# detector_t85-pu.net
KiCad netlist of a schematic drawn in EAGLE
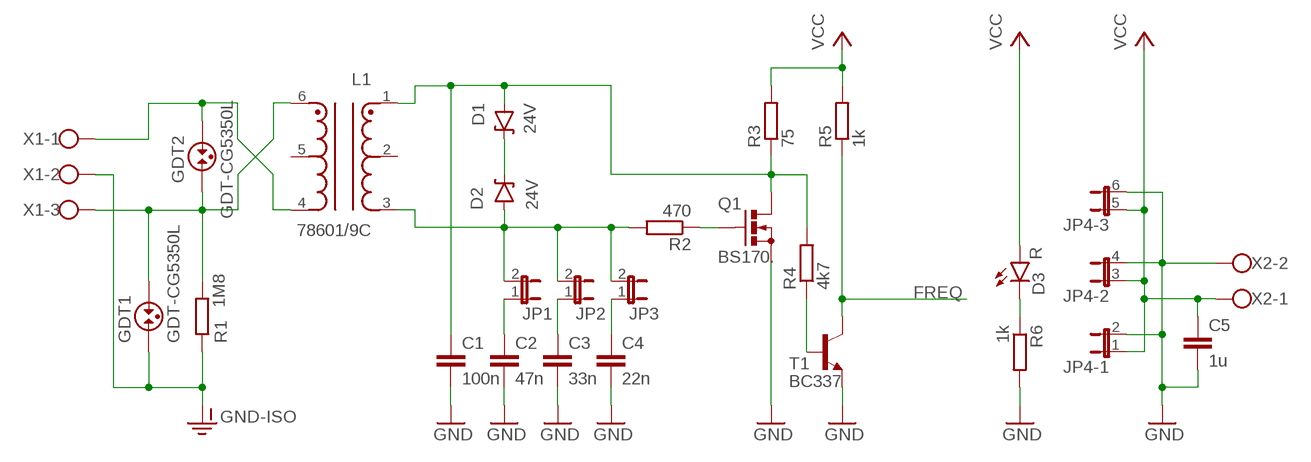
[diagram p0: schematic, sheet 1]
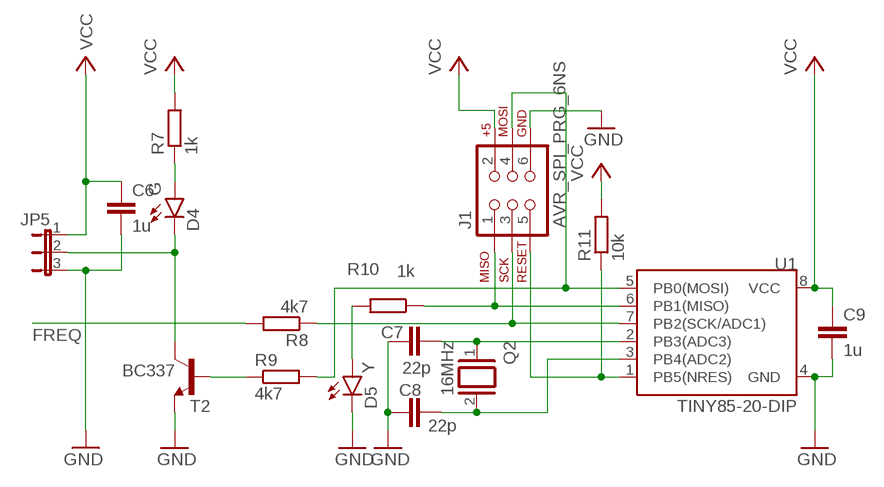
[diagram p1: schematic, sheet 2]

(export (version "E")
  (design (tool "Eeschema 10.0.6"))
  (components
    (comp (ref "C1")
      (value "100n")
      (footprint "eagle-import:C050-024X044")
      (libsource (lib "eagle-import") (part "resistor_C-EU050-024X044"))
    )
    (comp (ref "C2")
      (value "47n")
      (footprint "eagle-import:C050-024X044")
      (libsource (lib "eagle-import") (part "resistor_C-EU050-024X044"))
    )
    (comp (ref "C3")
      (value "33n")
      (footprint "eagle-import:C050-024X044")
      (libsource (lib "eagle-import") (part "resistor_C-EU050-024X044"))
    )
    (comp (ref "C4")
      (value "22n")
      (footprint "eagle-import:C050-024X044")
      (libsource (lib "eagle-import") (part "resistor_C-EU050-024X044"))
    )
    (comp (ref "C5")
      (value "1u")
      (footprint "eagle-import:C050-025X075")
      (libsource (lib "eagle-import") (part "C-EU050-025X075"))
    )
    (comp (ref "D1")
      (value "24V")
      (footprint "eagle-import:DIODE-BZT52")
      (libsource (lib "eagle-import") (part "DIODE-ZENER"))
    )
    (comp (ref "D2")
      (value "24V")
      (footprint "eagle-import:DIODE-BZT52")
      (libsource (lib "eagle-import") (part "DIODE-ZENER"))
    )
    (comp (ref "D3")
      (value "R")
      (footprint "eagle-import:LED3MM")
      (libsource (lib "eagle-import") (part "LED3MM"))
    )
    (comp (ref "GDT1")
      (value "GDT-CG5350L")
      (footprint "eagle-import:CG5350L")
      (libsource (lib "eagle-import") (part "GDT-CG5350L"))
    )
    (comp (ref "GDT2")
      (value "GDT-CG5350L")
      (footprint "eagle-import:CG5350L")
      (libsource (lib "eagle-import") (part "GDT-CG5350L"))
    )
    (comp (ref "JP1")
      (value "JUMPER-2PTH")
      (footprint "eagle-import:1X02")
      (libsource (lib "eagle-import") (part "JUMPER-2PTH"))
    )
    (comp (ref "JP2")
      (value "JUMPER-2PTH")
      (footprint "eagle-import:1X02")
      (libsource (lib "eagle-import") (part "JUMPER-2PTH"))
    )
    (comp (ref "JP3")
      (value "JUMPER-2PTH")
      (footprint "eagle-import:1X02")
      (libsource (lib "eagle-import") (part "JUMPER-2PTH"))
    )
    (comp (ref "JP4")
      (value "JP3QE")
      (footprint "eagle-import:JP3Q")
      (libsource (lib "eagle-import") (part "JP3QE"))
    )
    (comp (ref "L1")
      (value "78601/9C")
      (footprint "eagle-import:78601_9C")
      (libsource (lib "eagle-import") (part "78601/9C"))
    )
    (comp (ref "Q1")
      (value "BS170.")
      (footprint "eagle-import:TO92-DGS")
      (libsource (lib "eagle-import") (part "BS170."))
    )
    (comp (ref "R1")
      (value "1M8")
      (footprint "eagle-import:0204_5")
      (libsource (lib "eagle-import") (part "R-EU_0204/5"))
    )
    (comp (ref "R2")
      (value "470")
      (footprint "eagle-import:0204_5")
      (libsource (lib "eagle-import") (part "R-EU_0204/5"))
    )
    (comp (ref "R3")
      (value "75")
      (footprint "eagle-import:0204_7")
      (libsource (lib "eagle-import") (part "R-EU_0204/7"))
    )
    (comp (ref "R4")
      (value "4k7")
      (footprint "eagle-import:0204_5")
      (libsource (lib "eagle-import") (part "R-EU_0204/5"))
    )
    (comp (ref "R5")
      (value "1k")
      (footprint "eagle-import:0204_5")
      (libsource (lib "eagle-import") (part "R-EU_0204/5"))
    )
    (comp (ref "R6")
      (value "1k")
      (footprint "eagle-import:0204_5")
      (libsource (lib "eagle-import") (part "R-EU_0204/5"))
    )
    (comp (ref "T1")
      (value "BC337")
      (footprint "eagle-import:TO92-CBE")
      (libsource (lib "eagle-import") (part "-NPN-TO92-CBEBC337"))
    )
    (comp (ref "X1")
      (value "W237-103")
      (footprint "eagle-import:W237-103")
      (fields (field (name "MPN") "237-103"))
      (libsource (lib "eagle-import") (part "W237-103"))
    )
    (comp (ref "X2")
      (value "W237-102")
      (footprint "eagle-import:W237-102")
      (fields (field (name "MPN") "237-102"))
      (libsource (lib "eagle-import") (part "W237-102"))
    )
    (comp (ref "C6")
      (value "1u")
      (footprint "eagle-import:C050-025X075")
      (libsource (lib "eagle-import") (part "C-EU050-025X075"))
    )
    (comp (ref "C7")
      (value "22p")
      (footprint "eagle-import:CAP-PTH-SMALL2")
      (libsource (lib "eagle-import") (part "CAPPTH2"))
    )
    (comp (ref "C8")
      (value "22p")
      (footprint "eagle-import:CAP-PTH-SMALL2")
      (libsource (lib "eagle-import") (part "CAPPTH2"))
    )
    (comp (ref "C9")
      (value "1u")
      (footprint "eagle-import:C050-025X075")
      (libsource (lib "eagle-import") (part "C-EU050-025X075"))
    )
    (comp (ref "D4")
      (value "G")
      (footprint "eagle-import:LED3MM")
      (libsource (lib "eagle-import") (part "LED3MM"))
    )
    (comp (ref "D5")
      (value "Y")
      (footprint "eagle-import:LED3MM")
      (libsource (lib "eagle-import") (part "LED3MM"))
    )
    (comp (ref "J1")
      (value "AVR_SPI_PRG_6NS")
      (footprint "eagle-import:2X3-NS")
      (libsource (lib "eagle-import") (part "AVR_SPI_PRG_6NS"))
    )
    (comp (ref "JP5")
      (value "JP2E")
      (footprint "eagle-import:JP2")
      (libsource (lib "eagle-import") (part "JP2E"))
    )
    (comp (ref "Q2")
      (value "16MHz")
      (footprint "eagle-import:QS")
      (libsource (lib "eagle-import") (part "XTAL/S"))
    )
    (comp (ref "R7")
      (value "1k")
      (footprint "eagle-import:0204_5")
      (libsource (lib "eagle-import") (part "R-EU_0204/5"))
    )
    (comp (ref "R8")
      (value "4k7")
      (footprint "eagle-import:0204_5")
      (libsource (lib "eagle-import") (part "R-EU_0204/5"))
    )
    (comp (ref "R9")
      (value "4k7")
      (footprint "eagle-import:0204_5")
      (libsource (lib "eagle-import") (part "R-EU_0204/5"))
    )
    (comp (ref "R10")
      (value "1k")
      (footprint "eagle-import:0204_5")
      (libsource (lib "eagle-import") (part "R-EU_0204/5"))
    )
    (comp (ref "R11")
      (value "10k")
      (footprint "eagle-import:0204_5")
      (libsource (lib "eagle-import") (part "R-EU_0204/5"))
    )
    (comp (ref "T2")
      (value "BC337")
      (footprint "eagle-import:TO92-CBE")
      (libsource (lib "eagle-import") (part "-NPN-TO92-CBEBC337"))
    )
    (comp (ref "U1")
      (value "TINY85-20-DIP")
      (footprint "eagle-import:DIP08")
      (libsource (lib "eagle-import") (part "ATTINY45TINY45-20-DIP"))
    )
  )
  (nets
    (net (code "1") (name "FREQ") (class "Default")
      (node (ref "R5") (pin "1") (pinfunction "1_1") (pintype "passive"))
      (node (ref "R8") (pin "2") (pinfunction "2_2") (pintype "passive"))
      (node (ref "T1") (pin "C") (pinfunction "C_C") (pintype "passive"))
    )
    (net (code "2") (name "GND") (class "Default")
      (node (ref "C1") (pin "2") (pinfunction "2_2") (pintype "passive"))
      (node (ref "C2") (pin "2") (pinfunction "2_2") (pintype "passive"))
      (node (ref "C3") (pin "2") (pinfunction "2_2") (pintype "passive"))
      (node (ref "C4") (pin "2") (pinfunction "2_2") (pintype "passive"))
      (node (ref "C5") (pin "2") (pinfunction "2_2") (pintype "passive"))
      (node (ref "C6") (pin "2") (pinfunction "2_2") (pintype "passive"))
      (node (ref "C7") (pin "1") (pinfunction "1_1") (pintype "passive"))
      (node (ref "C8") (pin "1") (pinfunction "1_1") (pintype "passive"))
      (node (ref "C9") (pin "2") (pinfunction "2_2") (pintype "passive"))
      (node (ref "D5") (pin "K") (pinfunction "C_K") (pintype "passive"))
      (node (ref "J1") (pin "6") (pinfunction "6_6") (pintype "passive"))
      (node (ref "JP4") (pin "2") (pinfunction "2_2") (pintype "passive"))
      (node (ref "JP4") (pin "4") (pinfunction "2_4") (pintype "passive"))
      (node (ref "JP4") (pin "6") (pinfunction "2_6") (pintype "passive"))
      (node (ref "JP5") (pin "3") (pinfunction "3_3") (pintype "passive"))
      (node (ref "Q1") (pin "S") (pinfunction "S_S") (pintype "passive"))
      (node (ref "R6") (pin "2") (pinfunction "2_2") (pintype "passive"))
      (node (ref "T1") (pin "E") (pinfunction "E_E") (pintype "passive"))
      (node (ref "T2") (pin "E") (pinfunction "E_E") (pintype "passive"))
      (node (ref "U1") (pin "4") (pinfunction "GND_4") (pintype "bidirectional"))
      (node (ref "X2") (pin "2") (pinfunction "KL_2") (pintype "passive"))
    )
    (net (code "3") (name "GND-ISO") (class "Default")
      (node (ref "GDT1") (pin "1") (pinfunction "1_1") (pintype "passive"))
      (node (ref "R1") (pin "1") (pinfunction "1_1") (pintype "passive"))
      (node (ref "X1") (pin "2") (pinfunction "KL_2") (pintype "passive"))
    )
    (net (code "4") (name "Net-(C1-Pad1)") (class "Default")
      (node (ref "C1") (pin "1") (pinfunction "1_1") (pintype "passive"))
      (node (ref "D1") (pin "A") (pinfunction "A_A") (pintype "passive"))
      (node (ref "L1") (pin "1") (pinfunction "1_1") (pintype "passive"))
      (node (ref "Q1") (pin "D") (pinfunction "D_D") (pintype "passive"))
      (node (ref "R3") (pin "1") (pinfunction "1_1") (pintype "passive"))
      (node (ref "R4") (pin "2") (pinfunction "2_2") (pintype "passive"))
    )
    (net (code "5") (name "Net-(C2-Pad1)") (class "Default")
      (node (ref "C2") (pin "1") (pinfunction "1_1") (pintype "passive"))
      (node (ref "JP1") (pin "1") (pinfunction "1_1") (pintype "passive"))
    )
    (net (code "6") (name "Net-(C3-Pad1)") (class "Default")
      (node (ref "C3") (pin "1") (pinfunction "1_1") (pintype "passive"))
      (node (ref "JP2") (pin "1") (pinfunction "1_1") (pintype "passive"))
    )
    (net (code "7") (name "Net-(C4-Pad1)") (class "Default")
      (node (ref "C4") (pin "1") (pinfunction "1_1") (pintype "passive"))
      (node (ref "JP3") (pin "1") (pinfunction "1_1") (pintype "passive"))
    )
    (net (code "8") (name "Net-(D1-PadC)") (class "Default")
      (node (ref "D1") (pin "C") (pinfunction "C_C") (pintype "passive"))
      (node (ref "D2") (pin "C") (pinfunction "C_C") (pintype "passive"))
    )
    (net (code "9") (name "Net-(D2-PadA)") (class "Default")
      (node (ref "D2") (pin "A") (pinfunction "A_A") (pintype "passive"))
      (node (ref "JP1") (pin "2") (pinfunction "2_2") (pintype "passive"))
      (node (ref "JP2") (pin "2") (pinfunction "2_2") (pintype "passive"))
      (node (ref "JP3") (pin "2") (pinfunction "2_2") (pintype "passive"))
      (node (ref "L1") (pin "3") (pinfunction "3_3") (pintype "passive"))
      (node (ref "R2") (pin "2") (pinfunction "2_2") (pintype "passive"))
    )
    (net (code "10") (name "Net-(D3-C)") (class "Default")
      (node (ref "D3") (pin "K") (pinfunction "C_K") (pintype "passive"))
      (node (ref "R6") (pin "1") (pinfunction "1_1") (pintype "passive"))
    )
    (net (code "11") (name "Net-(D4-C)") (class "Default")
      (node (ref "D4") (pin "K") (pinfunction "C_K") (pintype "passive"))
      (node (ref "JP5") (pin "2") (pinfunction "2_2") (pintype "passive"))
      (node (ref "T2") (pin "C") (pinfunction "C_C") (pintype "passive"))
    )
    (net (code "12") (name "Net-(D4-PadA)") (class "Default")
      (node (ref "D4") (pin "A") (pinfunction "A_A") (pintype "passive"))
      (node (ref "R7") (pin "1") (pinfunction "1_1") (pintype "passive"))
    )
    (net (code "13") (name "Net-(D5-PadA)") (class "Default")
      (node (ref "D5") (pin "A") (pinfunction "A_A") (pintype "passive"))
      (node (ref "R10") (pin "2") (pinfunction "2_2") (pintype "passive"))
    )
    (net (code "14") (name "Net-(Q1-PadG)") (class "Default")
      (node (ref "Q1") (pin "G") (pinfunction "G_G") (pintype "passive"))
      (node (ref "R2") (pin "1") (pinfunction "1_1") (pintype "passive"))
    )
    (net (code "15") (name "Net-(R4-Pad1)") (class "Default")
      (node (ref "R4") (pin "1") (pinfunction "1_1") (pintype "passive"))
      (node (ref "T1") (pin "B") (pinfunction "B_B") (pintype "passive"))
    )
    (net (code "16") (name "Net-(R9-Pad1)") (class "Default")
      (node (ref "R9") (pin "1") (pinfunction "1_1") (pintype "passive"))
      (node (ref "T2") (pin "B") (pinfunction "B_B") (pintype "passive"))
    )
    (net (code "17") (name "Net-(U1-PB0(MOSI))") (class "Default")
      (node (ref "J1") (pin "4") (pinfunction "4_4") (pintype "passive"))
      (node (ref "R9") (pin "2") (pinfunction "2_2") (pintype "passive"))
      (node (ref "U1") (pin "5") (pinfunction "PB0(MOSI)_5") (pintype "bidirectional"))
    )
    (net (code "18") (name "Net-(U1-PB1(MISO))") (class "Default")
      (node (ref "J1") (pin "1") (pinfunction "1_1") (pintype "passive"))
      (node (ref "R10") (pin "1") (pinfunction "1_1") (pintype "passive"))
      (node (ref "U1") (pin "6") (pinfunction "PB1(MISO)_6") (pintype "bidirectional"))
    )
    (net (code "19") (name "Net-(U1-PB2(SCK{slash}ADC1))") (class "Default")
      (node (ref "J1") (pin "3") (pinfunction "3_3") (pintype "passive"))
      (node (ref "R8") (pin "1") (pinfunction "1_1") (pintype "passive"))
      (node (ref "U1") (pin "7") (pinfunction "PB2(SCK/ADC1)_7") (pintype "bidirectional"))
    )
    (net (code "20") (name "Net-(U1-PB3(ADC3))") (class "Default")
      (node (ref "C7") (pin "2") (pinfunction "2_2") (pintype "passive"))
      (node (ref "Q2") (pin "1") (pinfunction "1_1") (pintype "passive"))
      (node (ref "U1") (pin "2") (pinfunction "PB3(ADC3)_2") (pintype "bidirectional"))
    )
    (net (code "21") (name "Net-(U1-PB4(ADC2))") (class "Default")
      (node (ref "C8") (pin "2") (pinfunction "2_2") (pintype "passive"))
      (node (ref "Q2") (pin "2") (pinfunction "2_2") (pintype "passive"))
      (node (ref "U1") (pin "3") (pinfunction "PB4(ADC2)_3") (pintype "bidirectional"))
    )
    (net (code "22") (name "Net-(U1-PB5(NRES))") (class "Default")
      (node (ref "J1") (pin "5") (pinfunction "5_5") (pintype "passive"))
      (node (ref "R11") (pin "1") (pinfunction "1_1") (pintype "passive"))
      (node (ref "U1") (pin "1") (pinfunction "PB5(NRES)_1") (pintype "bidirectional"))
    )
    (net (code "23") (name "Net-(X1A-KL)") (class "Default")
      (node (ref "GDT2") (pin "2") (pinfunction "2_2") (pintype "passive"))
      (node (ref "L1") (pin "4") (pinfunction "4_4") (pintype "passive"))
      (node (ref "X1") (pin "1") (pinfunction "KL_1") (pintype "passive"))
    )
    (net (code "24") (name "Net-(X1C-KL)") (class "Default")
      (node (ref "GDT1") (pin "2") (pinfunction "2_2") (pintype "passive"))
      (node (ref "GDT2") (pin "1") (pinfunction "1_1") (pintype "passive"))
      (node (ref "L1") (pin "6") (pinfunction "6_6") (pintype "passive"))
      (node (ref "R1") (pin "2") (pinfunction "2_2") (pintype "passive"))
      (node (ref "X1") (pin "3") (pinfunction "KL_3") (pintype "passive"))
    )
    (net (code "25") (name "VCC") (class "Default")
      (node (ref "C5") (pin "1") (pinfunction "1_1") (pintype "passive"))
      (node (ref "C6") (pin "1") (pinfunction "1_1") (pintype "passive"))
      (node (ref "C9") (pin "1") (pinfunction "1_1") (pintype "passive"))
      (node (ref "D3") (pin "A") (pinfunction "A_A") (pintype "passive"))
      (node (ref "J1") (pin "2") (pinfunction "2_2") (pintype "passive"))
      (node (ref "JP4") (pin "1") (pinfunction "1_1") (pintype "passive"))
      (node (ref "JP4") (pin "3") (pinfunction "1_3") (pintype "passive"))
      (node (ref "JP4") (pin "5") (pinfunction "1_5") (pintype "passive"))
      (node (ref "JP5") (pin "1") (pinfunction "1_1") (pintype "passive"))
      (node (ref "R11") (pin "2") (pinfunction "2_2") (pintype "passive"))
      (node (ref "R3") (pin "2") (pinfunction "2_2") (pintype "passive"))
      (node (ref "R5") (pin "2") (pinfunction "2_2") (pintype "passive"))
      (node (ref "R7") (pin "2") (pinfunction "2_2") (pintype "passive"))
      (node (ref "U1") (pin "8") (pinfunction "VCC_8") (pintype "bidirectional"))
      (node (ref "X2") (pin "1") (pinfunction "KL_1") (pintype "passive"))
    )
    (net (code "26") (name "unconnected-(L1-Pad2)") (class "Default")
      (node (ref "L1") (pin "2") (pinfunction "2_2") (pintype "passive"))
    )
    (net (code "27") (name "unconnected-(L1-Pad5)") (class "Default")
      (node (ref "L1") (pin "5") (pinfunction "5_5") (pintype "passive"))
    )
  )
)
